# ICS40300-Silicon-Mic_Rev-C.net
KiCad netlist of a schematic drawn in EAGLE
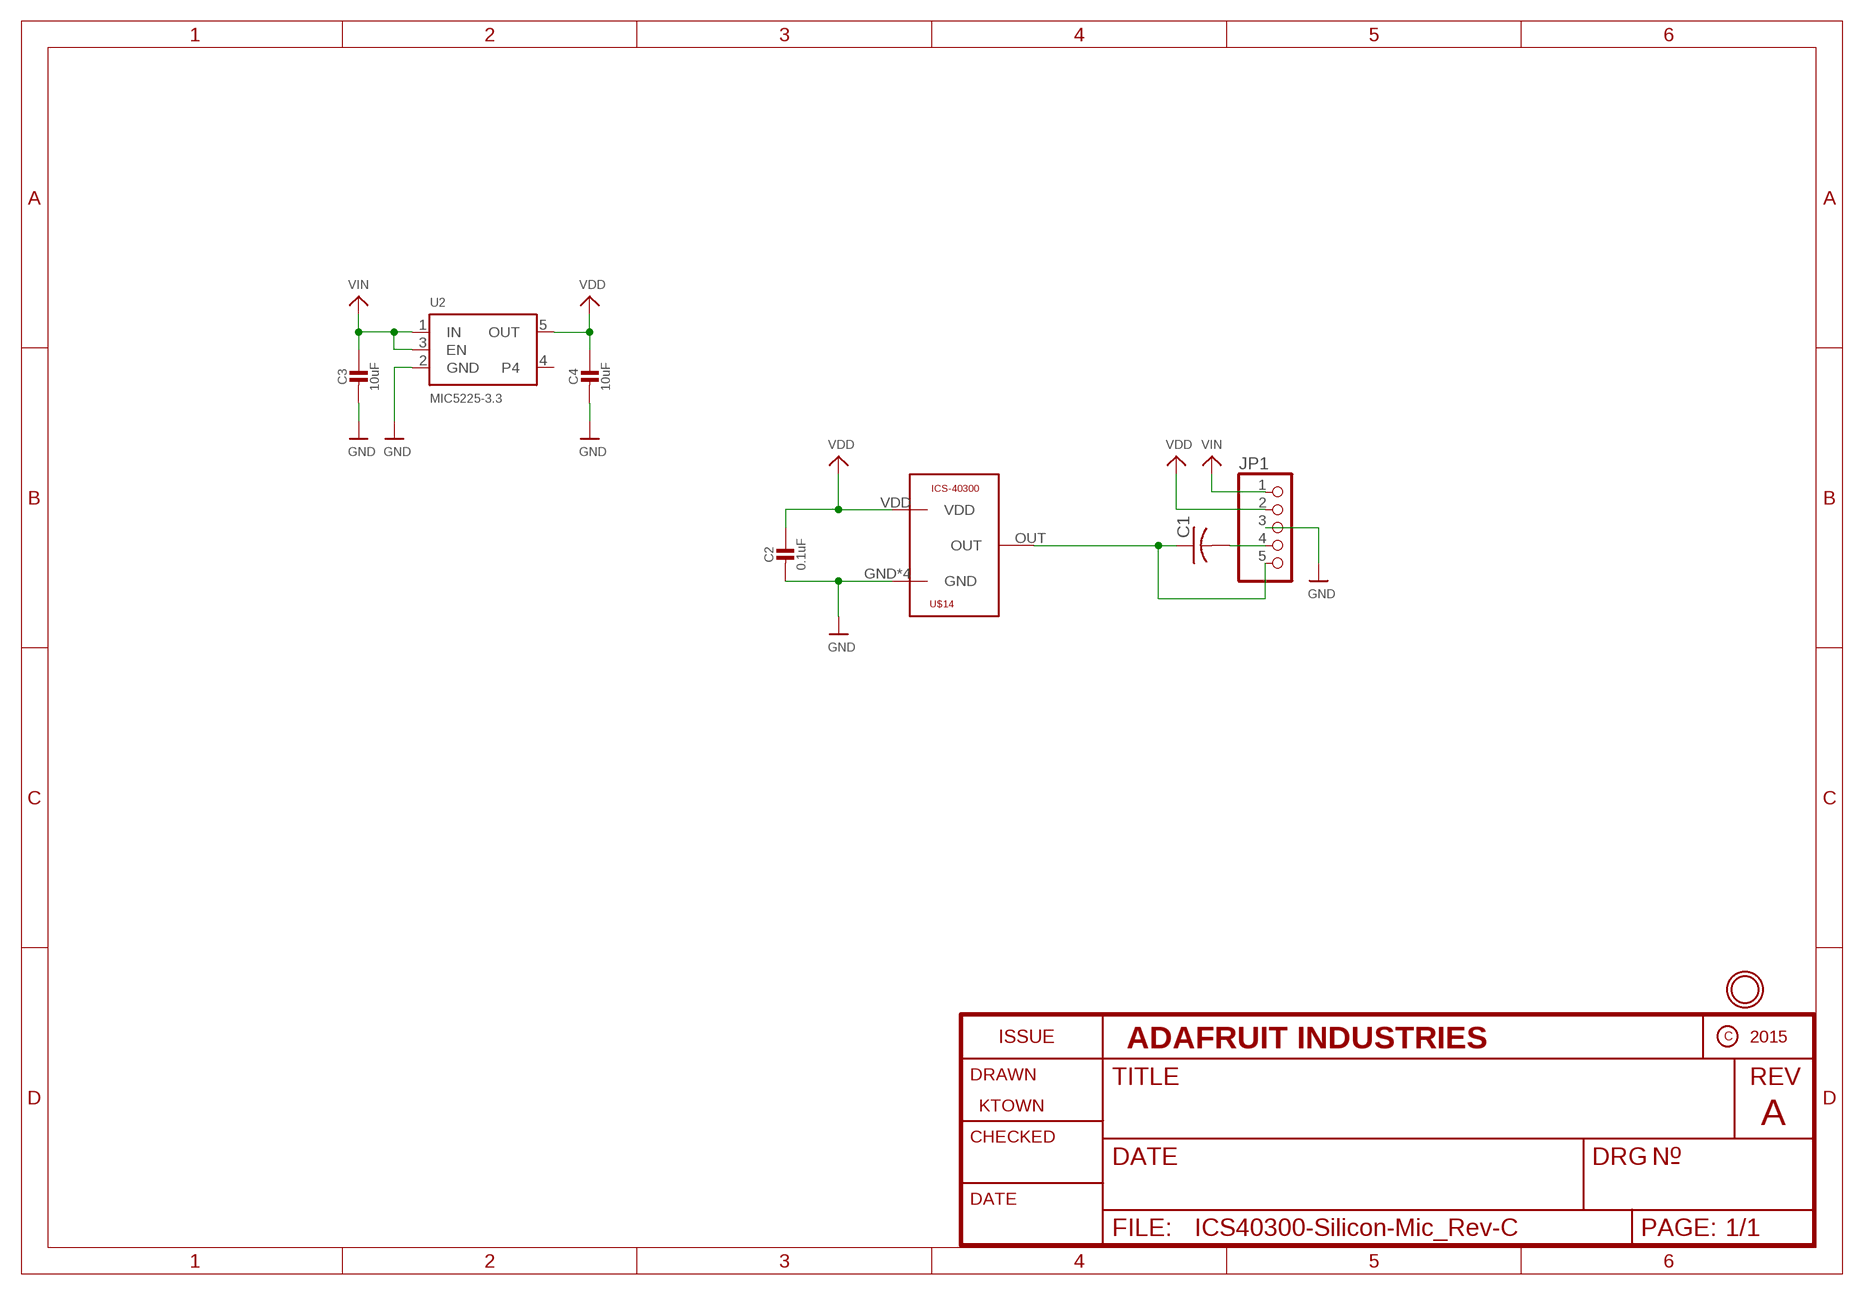
[diagram p0: schematic, sheet 1]

(export (version "E")
  (design (tool "Eeschema 10.0.6"))
  (components
    (comp (ref "C1")
      (value "C-US")
      (footprint "eagle-import:CT7343")
      (libsource (lib "eagle-import") (part "C-US"))
    )
    (comp (ref "C2")
      (value "0.1uF")
      (footprint "eagle-import:0805-NO")
      (libsource (lib "eagle-import") (part "CAP_CERAMIC0805-NOOUTLINE"))
    )
    (comp (ref "C3")
      (value "10uF")
      (footprint "eagle-import:0805-NO")
      (libsource (lib "eagle-import") (part "CAP_CERAMIC0805-NOOUTLINE"))
    )
    (comp (ref "C4")
      (value "10uF")
      (footprint "eagle-import:0805-NO")
      (libsource (lib "eagle-import") (part "CAP_CERAMIC0805-NOOUTLINE"))
    )
    (comp (ref "JP1")
      (value "HEADER-1X576MIL")
      (footprint "eagle-import:1X05_ROUND_76")
      (libsource (lib "eagle-import") (part "HEADER-1X576MIL"))
    )
    (comp (ref "U$12")
      (value "MOUNTINGHOLE2.5")
      (footprint "eagle-import:MOUNTINGHOLE_2.5_PLATED")
      (libsource (lib "eagle-import") (part "MOUNTINGHOLE2.5"))
    )
    (comp (ref "U$14")
      (value "ICS-40300")
      (footprint "eagle-import:ICS-40300")
      (libsource (lib "eagle-import") (part "ICS-40300"))
    )
    (comp (ref "U2")
      (value "MIC5225-3.3")
      (footprint "eagle-import:SOT23-5")
      (libsource (lib "eagle-import") (part "VREG_SOT23-5"))
    )
  )
  (nets
    (net (code "1") (name "GND") (class "Default")
      (node (ref "C2") (pin "2") (pinfunction "2_2") (pintype "passive"))
      (node (ref "C3") (pin "2") (pinfunction "2_2") (pintype "passive"))
      (node (ref "C4") (pin "2") (pinfunction "2_2") (pintype "passive"))
      (node (ref "JP1") (pin "3") (pinfunction "3_3") (pintype "passive"))
      (node (ref "U$14") (pin "GND") (pinfunction "GND_GND") (pintype "bidirectional"))
      (node (ref "U$14") (pin "GND1") (pinfunction "GND_GND1") (pintype "bidirectional"))
      (node (ref "U$14") (pin "GND2") (pinfunction "GND_GND2") (pintype "bidirectional"))
      (node (ref "U$14") (pin "GND3") (pinfunction "GND_GND3") (pintype "bidirectional"))
      (node (ref "U2") (pin "2") (pinfunction "GND_2") (pintype "power_in"))
    )
    (net (code "2") (name "Net-(C1-1)") (class "Default")
      (node (ref "C1") (pin "+") (pinfunction "1_+") (pintype "passive"))
      (node (ref "JP1") (pin "5") (pinfunction "5_5") (pintype "passive"))
      (node (ref "U$14") (pin "OUT") (pinfunction "OUT_OUT") (pintype "bidirectional"))
    )
    (net (code "3") (name "Net-(C1-2)") (class "Default")
      (node (ref "C1") (pin "-") (pinfunction "2_-") (pintype "passive"))
      (node (ref "JP1") (pin "4") (pinfunction "4_4") (pintype "passive"))
    )
    (net (code "4") (name "VDD") (class "Default")
      (node (ref "C2") (pin "1") (pinfunction "1_1") (pintype "passive"))
      (node (ref "C4") (pin "1") (pinfunction "1_1") (pintype "passive"))
      (node (ref "JP1") (pin "2") (pinfunction "2_2") (pintype "passive"))
      (node (ref "U$14") (pin "VDD") (pinfunction "VDD_VDD") (pintype "bidirectional"))
      (node (ref "U2") (pin "5") (pinfunction "OUT_5") (pintype "power_in"))
    )
    (net (code "5") (name "VIN") (class "Default")
      (node (ref "C3") (pin "1") (pinfunction "1_1") (pintype "passive"))
      (node (ref "JP1") (pin "1") (pinfunction "1_1") (pintype "passive"))
      (node (ref "U2") (pin "1") (pinfunction "IN_1") (pintype "power_in"))
      (node (ref "U2") (pin "3") (pinfunction "EN_3") (pintype "input"))
    )
    (net (code "6") (name "unconnected-(U2-P4-Pad4)") (class "Default")
      (node (ref "U2") (pin "4") (pinfunction "P4_4") (pintype "bidirectional"))
    )
  )
)
